# Connector_Sheet.net
KiCad netlist of a schematic drawn in Altium Designer
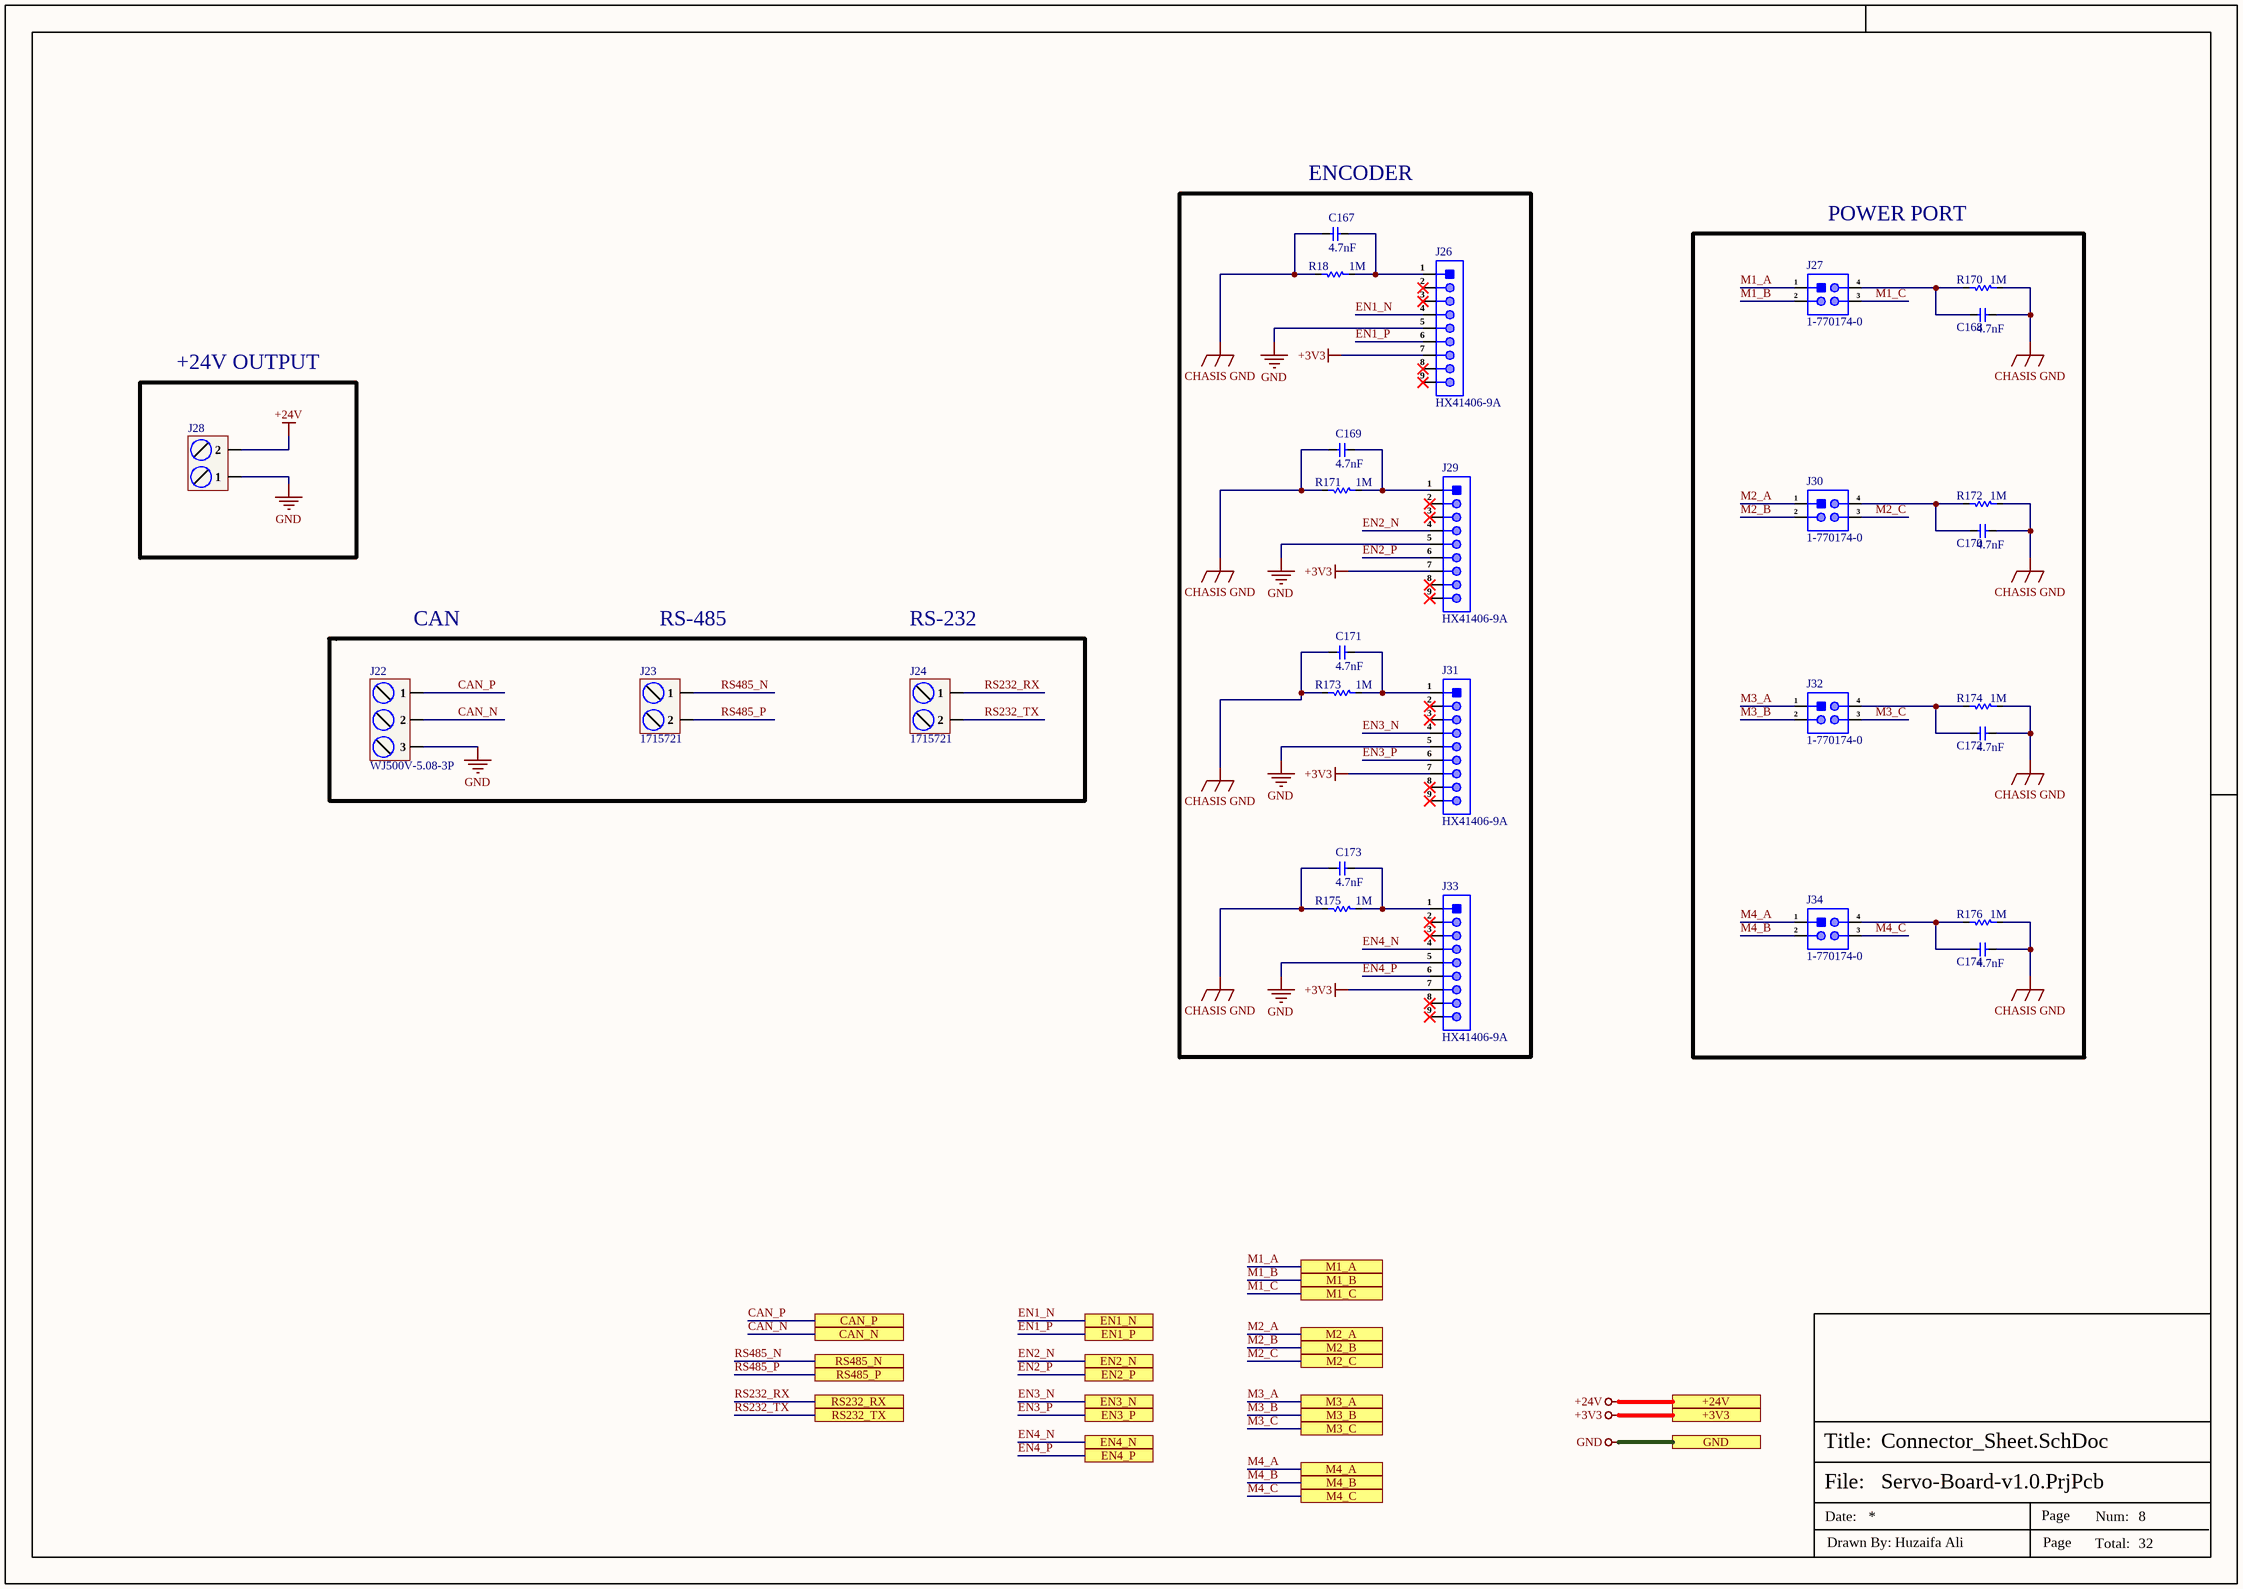
[diagram p0: Connector_Sheet.SchDoc]

(export (version "E")
  (design (tool "Eeschema 10.0.6"))
  (components
    (comp (ref "C167")
      (value "4.7nF")
      (footprint "Cap-0603")
      (description "CAP CER 4700PF 50V C0G/NPO 0603")
      (fields
        (field (name "MANUFACTURER") "Yageo")
        (field (name "MANUFACTURER PART NUMBER") "CC0603JRNPO9BN472")
      )
      (libsource (lib "eSpark_centralized_Library(2022)") (part "CC0603JRNPO9BN472"))
    )
    (comp (ref "C168")
      (value "4.7nF")
      (footprint "Cap-0603")
      (description "CAP CER 4700PF 50V C0G/NPO 0603")
      (fields
        (field (name "MANUFACTURER") "Yageo")
        (field (name "MANUFACTURER PART NUMBER") "CC0603JRNPO9BN472")
      )
      (libsource (lib "eSpark_centralized_Library(2022)") (part "CC0603JRNPO9BN472"))
    )
    (comp (ref "C169")
      (value "4.7nF")
      (footprint "Cap-0603")
      (description "CAP CER 4700PF 50V C0G/NPO 0603")
      (fields
        (field (name "MANUFACTURER") "Yageo")
        (field (name "MANUFACTURER PART NUMBER") "CC0603JRNPO9BN472")
      )
      (libsource (lib "eSpark_centralized_Library(2022)") (part "CC0603JRNPO9BN472"))
    )
    (comp (ref "C170")
      (value "4.7nF")
      (footprint "Cap-0603")
      (description "CAP CER 4700PF 50V C0G/NPO 0603")
      (fields
        (field (name "MANUFACTURER") "Yageo")
        (field (name "MANUFACTURER PART NUMBER") "CC0603JRNPO9BN472")
      )
      (libsource (lib "eSpark_centralized_Library(2022)") (part "CC0603JRNPO9BN472"))
    )
    (comp (ref "C171")
      (value "4.7nF")
      (footprint "Cap-0603")
      (description "CAP CER 4700PF 50V C0G/NPO 0603")
      (fields
        (field (name "MANUFACTURER") "Yageo")
        (field (name "MANUFACTURER PART NUMBER") "CC0603JRNPO9BN472")
      )
      (libsource (lib "eSpark_centralized_Library(2022)") (part "CC0603JRNPO9BN472"))
    )
    (comp (ref "C172")
      (value "4.7nF")
      (footprint "Cap-0603")
      (description "CAP CER 4700PF 50V C0G/NPO 0603")
      (fields
        (field (name "MANUFACTURER") "Yageo")
        (field (name "MANUFACTURER PART NUMBER") "CC0603JRNPO9BN472")
      )
      (libsource (lib "eSpark_centralized_Library(2022)") (part "CC0603JRNPO9BN472"))
    )
    (comp (ref "C173")
      (value "4.7nF")
      (footprint "Cap-0603")
      (description "CAP CER 4700PF 50V C0G/NPO 0603")
      (fields
        (field (name "MANUFACTURER") "Yageo")
        (field (name "MANUFACTURER PART NUMBER") "CC0603JRNPO9BN472")
      )
      (libsource (lib "eSpark_centralized_Library(2022)") (part "CC0603JRNPO9BN472"))
    )
    (comp (ref "C174")
      (value "4.7nF")
      (footprint "Cap-0603")
      (description "CAP CER 4700PF 50V C0G/NPO 0603")
      (fields
        (field (name "MANUFACTURER") "Yageo")
        (field (name "MANUFACTURER PART NUMBER") "CC0603JRNPO9BN472")
      )
      (libsource (lib "eSpark_centralized_Library(2022)") (part "CC0603JRNPO9BN472"))
    )
    (comp (ref "J22")
      (value "WJ500V-5.08-3P")
      (footprint "WJ500V-5.08-3P")
      (fields (field (name "MANUFACTURER") "Ningbo Kangnex Elec") (field (name "LCSC PART NUMBER") "C72334"))
      (libsource (lib "eSpark Libraries") (part "WJ500V-5.08-3P"))
    )
    (comp (ref "J23")
      (value "1715721")
      (footprint "1715721")
      (description "TERM BLK 2P SIDE ENT 5.08MM PCB")
      (fields (field (name "MANUFACTURER") "Phoenix Contact"))
      (libsource (lib "eSpark Libraries") (part "1715721"))
    )
    (comp (ref "J24")
      (value "1715721")
      (footprint "1715721")
      (description "TERM BLK 2P SIDE ENT 5.08MM PCB")
      (fields (field (name "MANUFACTURER") "Phoenix Contact"))
      (libsource (lib "eSpark Libraries") (part "1715721"))
    )
    (comp (ref "J26")
      (value "HX41406-9A")
      (footprint "HX41406-9A")
      (description "3x3P 9P 3 4.14mm 4.14mm 3 -25℃~+105℃ 8A Straight Plugin,P=4.14mm Wire To Board Connector ROHS")
      (fields
        (field (name "MANUFACTURER") "HX(Zhejiang Yueqing Hongxing Elec)")
        (field (name "LCSC PART NUMBER") "C704507")
      )
      (libsource (lib "eSpark Libraries") (part "HX41406-9A"))
    )
    (comp (ref "J27")
      (value "1-770174-0")
      (footprint "1-770174-0")
      (description "CONN HEADER VERT 4POS 4.14MM")
      (fields (field (name "MANUFACTURER") "TE Connectivity"))
      (libsource (lib "eSpark Libraries") (part "1-770174-0"))
    )
    (comp (ref "J28")
      (value "MXHB9500-9.5-02P-BK01-Cu-S-A")
      (footprint "MXHB9500-9.5-02P-BK01-Cu-S-A")
      (fields (field (name "MANUFACTURER") "MAX") (field (name "LCSC PART NUMBER") "C7542168"))
      (libsource (lib "eSpark Libraries") (part "MXHB9500-9.5-02P-BK01-Cu-S-A"))
    )
    (comp (ref "J29")
      (value "HX41406-9A")
      (footprint "HX41406-9A")
      (description "3x3P 9P 3 4.14mm 4.14mm 3 -25℃~+105℃ 8A Straight Plugin,P=4.14mm Wire To Board Connector ROHS")
      (fields
        (field (name "MANUFACTURER") "HX(Zhejiang Yueqing Hongxing Elec)")
        (field (name "LCSC PART NUMBER") "C704507")
      )
      (libsource (lib "eSpark Libraries") (part "HX41406-9A"))
    )
    (comp (ref "J30")
      (value "1-770174-0")
      (footprint "1-770174-0")
      (description "CONN HEADER VERT 4POS 4.14MM")
      (fields (field (name "MANUFACTURER") "TE Connectivity"))
      (libsource (lib "eSpark Libraries") (part "1-770174-0"))
    )
    (comp (ref "J31")
      (value "HX41406-9A")
      (footprint "HX41406-9A")
      (description "3x3P 9P 3 4.14mm 4.14mm 3 -25℃~+105℃ 8A Straight Plugin,P=4.14mm Wire To Board Connector ROHS")
      (fields
        (field (name "MANUFACTURER") "HX(Zhejiang Yueqing Hongxing Elec)")
        (field (name "LCSC PART NUMBER") "C704507")
      )
      (libsource (lib "eSpark Libraries") (part "HX41406-9A"))
    )
    (comp (ref "J32")
      (value "1-770174-0")
      (footprint "1-770174-0")
      (description "CONN HEADER VERT 4POS 4.14MM")
      (fields (field (name "MANUFACTURER") "TE Connectivity"))
      (libsource (lib "eSpark Libraries") (part "1-770174-0"))
    )
    (comp (ref "J33")
      (value "HX41406-9A")
      (footprint "HX41406-9A")
      (description "3x3P 9P 3 4.14mm 4.14mm 3 -25℃~+105℃ 8A Straight Plugin,P=4.14mm Wire To Board Connector ROHS")
      (fields
        (field (name "MANUFACTURER") "HX(Zhejiang Yueqing Hongxing Elec)")
        (field (name "LCSC PART NUMBER") "C704507")
      )
      (libsource (lib "eSpark Libraries") (part "HX41406-9A"))
    )
    (comp (ref "J34")
      (value "1-770174-0")
      (footprint "1-770174-0")
      (description "CONN HEADER VERT 4POS 4.14MM")
      (fields (field (name "MANUFACTURER") "TE Connectivity"))
      (libsource (lib "eSpark Libraries") (part "1-770174-0"))
    )
    (comp (ref "R18")
      (value "1M")
      (footprint "Res-0402")
      (description "RES SMD 1M OHM 5% 1/16W 0402")
      (fields
        (field (name "MANUFACTURER") "Yageo")
        (field (name "MANUFACTURER PART NUMBER") "AF0402JR-071ML")
      )
      (libsource (lib "eSpark_centralized_Library(2022)") (part "AF0402JR-071ML"))
    )
    (comp (ref "R170")
      (value "1M")
      (footprint "Res-0402")
      (description "RES SMD 1M OHM 5% 1/16W 0402")
      (fields
        (field (name "MANUFACTURER") "Yageo")
        (field (name "MANUFACTURER PART NUMBER") "AF0402JR-071ML")
      )
      (libsource (lib "eSpark_centralized_Library(2022)") (part "AF0402JR-071ML"))
    )
    (comp (ref "R171")
      (value "1M")
      (footprint "Res-0402")
      (description "RES SMD 1M OHM 5% 1/16W 0402")
      (fields
        (field (name "MANUFACTURER") "Yageo")
        (field (name "MANUFACTURER PART NUMBER") "AF0402JR-071ML")
      )
      (libsource (lib "eSpark_centralized_Library(2022)") (part "AF0402JR-071ML"))
    )
    (comp (ref "R172")
      (value "1M")
      (footprint "Res-0402")
      (description "RES SMD 1M OHM 5% 1/16W 0402")
      (fields
        (field (name "MANUFACTURER") "Yageo")
        (field (name "MANUFACTURER PART NUMBER") "AF0402JR-071ML")
      )
      (libsource (lib "eSpark_centralized_Library(2022)") (part "AF0402JR-071ML"))
    )
    (comp (ref "R173")
      (value "1M")
      (footprint "Res-0402")
      (description "RES SMD 1M OHM 5% 1/16W 0402")
      (fields
        (field (name "MANUFACTURER") "Yageo")
        (field (name "MANUFACTURER PART NUMBER") "AF0402JR-071ML")
      )
      (libsource (lib "eSpark_centralized_Library(2022)") (part "AF0402JR-071ML"))
    )
    (comp (ref "R174")
      (value "1M")
      (footprint "Res-0402")
      (description "RES SMD 1M OHM 5% 1/16W 0402")
      (fields
        (field (name "MANUFACTURER") "Yageo")
        (field (name "MANUFACTURER PART NUMBER") "AF0402JR-071ML")
      )
      (libsource (lib "eSpark_centralized_Library(2022)") (part "AF0402JR-071ML"))
    )
    (comp (ref "R175")
      (value "1M")
      (footprint "Res-0402")
      (description "RES SMD 1M OHM 5% 1/16W 0402")
      (fields
        (field (name "MANUFACTURER") "Yageo")
        (field (name "MANUFACTURER PART NUMBER") "AF0402JR-071ML")
      )
      (libsource (lib "eSpark_centralized_Library(2022)") (part "AF0402JR-071ML"))
    )
    (comp (ref "R176")
      (value "1M")
      (footprint "Res-0402")
      (description "RES SMD 1M OHM 5% 1/16W 0402")
      (fields
        (field (name "MANUFACTURER") "Yageo")
        (field (name "MANUFACTURER PART NUMBER") "AF0402JR-071ML")
      )
      (libsource (lib "eSpark_centralized_Library(2022)") (part "AF0402JR-071ML"))
    )
  )
  (nets
    (net (code "1") (name "+3V3") (class "Default")
      (node (ref "J26") (pin "7") (pinfunction "7_7") (pintype "passive"))
      (node (ref "J29") (pin "7") (pinfunction "7_7") (pintype "passive"))
      (node (ref "J31") (pin "7") (pinfunction "7_7") (pintype "passive"))
      (node (ref "J33") (pin "7") (pinfunction "7_7") (pintype "passive"))
    )
    (net (code "2") (name "+24V") (class "Default")
      (node (ref "J28") (pin "2") (pinfunction "2_2") (pintype "passive"))
    )
    (net (code "3") (name "/CAN_N") (class "Default")
      (node (ref "J22") (pin "2") (pinfunction "2_2") (pintype "passive"))
    )
    (net (code "4") (name "/CAN_P") (class "Default")
      (node (ref "J22") (pin "1") (pinfunction "1_1") (pintype "passive"))
    )
    (net (code "5") (name "/EN1_N") (class "Default")
      (node (ref "J26") (pin "4") (pinfunction "4_4") (pintype "passive"))
    )
    (net (code "6") (name "/EN1_P") (class "Default")
      (node (ref "J26") (pin "6") (pinfunction "6_6") (pintype "passive"))
    )
    (net (code "7") (name "/EN2_N") (class "Default")
      (node (ref "J29") (pin "4") (pinfunction "4_4") (pintype "passive"))
    )
    (net (code "8") (name "/EN2_P") (class "Default")
      (node (ref "J29") (pin "6") (pinfunction "6_6") (pintype "passive"))
    )
    (net (code "9") (name "/EN3_N") (class "Default")
      (node (ref "J31") (pin "4") (pinfunction "4_4") (pintype "passive"))
    )
    (net (code "10") (name "/EN3_P") (class "Default")
      (node (ref "J31") (pin "6") (pinfunction "6_6") (pintype "passive"))
    )
    (net (code "11") (name "/EN4_N") (class "Default")
      (node (ref "J33") (pin "4") (pinfunction "4_4") (pintype "passive"))
    )
    (net (code "12") (name "/EN4_P") (class "Default")
      (node (ref "J33") (pin "6") (pinfunction "6_6") (pintype "passive"))
    )
    (net (code "13") (name "/M1_A") (class "Default")
      (node (ref "J27") (pin "1") (pinfunction "1_1") (pintype "passive"))
    )
    (net (code "14") (name "/M1_B") (class "Default")
      (node (ref "J27") (pin "2") (pinfunction "2_2") (pintype "passive"))
    )
    (net (code "15") (name "/M1_C") (class "Default")
      (node (ref "J27") (pin "3") (pinfunction "3_3") (pintype "passive"))
    )
    (net (code "16") (name "/M2_A") (class "Default")
      (node (ref "J30") (pin "1") (pinfunction "1_1") (pintype "passive"))
    )
    (net (code "17") (name "/M2_B") (class "Default")
      (node (ref "J30") (pin "2") (pinfunction "2_2") (pintype "passive"))
    )
    (net (code "18") (name "/M2_C") (class "Default")
      (node (ref "J30") (pin "3") (pinfunction "3_3") (pintype "passive"))
    )
    (net (code "19") (name "/M3_A") (class "Default")
      (node (ref "J32") (pin "1") (pinfunction "1_1") (pintype "passive"))
    )
    (net (code "20") (name "/M3_B") (class "Default")
      (node (ref "J32") (pin "2") (pinfunction "2_2") (pintype "passive"))
    )
    (net (code "21") (name "/M3_C") (class "Default")
      (node (ref "J32") (pin "3") (pinfunction "3_3") (pintype "passive"))
    )
    (net (code "22") (name "/M4_A") (class "Default")
      (node (ref "J34") (pin "1") (pinfunction "1_1") (pintype "passive"))
    )
    (net (code "23") (name "/M4_B") (class "Default")
      (node (ref "J34") (pin "2") (pinfunction "2_2") (pintype "passive"))
    )
    (net (code "24") (name "/M4_C") (class "Default")
      (node (ref "J34") (pin "3") (pinfunction "3_3") (pintype "passive"))
    )
    (net (code "25") (name "/RS232_RX") (class "Default")
      (node (ref "J24") (pin "1") (pinfunction "1_1") (pintype "passive"))
    )
    (net (code "26") (name "/RS232_TX") (class "Default")
      (node (ref "J24") (pin "2") (pinfunction "2_2") (pintype "passive"))
    )
    (net (code "27") (name "/RS485_N") (class "Default")
      (node (ref "J23") (pin "1") (pinfunction "1_1") (pintype "passive"))
    )
    (net (code "28") (name "/RS485_P") (class "Default")
      (node (ref "J23") (pin "2") (pinfunction "2_2") (pintype "passive"))
    )
    (net (code "29") (name "CHASIS GND") (class "Default")
      (node (ref "C167") (pin "2") (pinfunction "2_2") (pintype "passive"))
      (node (ref "C168") (pin "2") (pinfunction "2_2") (pintype "passive"))
      (node (ref "C169") (pin "2") (pinfunction "2_2") (pintype "passive"))
      (node (ref "C170") (pin "2") (pinfunction "2_2") (pintype "passive"))
      (node (ref "C171") (pin "2") (pinfunction "2_2") (pintype "passive"))
      (node (ref "C172") (pin "2") (pinfunction "2_2") (pintype "passive"))
      (node (ref "C173") (pin "2") (pinfunction "2_2") (pintype "passive"))
      (node (ref "C174") (pin "2") (pinfunction "2_2") (pintype "passive"))
      (node (ref "R170") (pin "2") (pinfunction "2_2") (pintype "passive"))
      (node (ref "R171") (pin "1") (pinfunction "1_1") (pintype "passive"))
      (node (ref "R172") (pin "2") (pinfunction "2_2") (pintype "passive"))
      (node (ref "R173") (pin "1") (pinfunction "1_1") (pintype "passive"))
      (node (ref "R174") (pin "2") (pinfunction "2_2") (pintype "passive"))
      (node (ref "R175") (pin "1") (pinfunction "1_1") (pintype "passive"))
      (node (ref "R176") (pin "2") (pinfunction "2_2") (pintype "passive"))
      (node (ref "R18") (pin "1") (pinfunction "1_1") (pintype "passive"))
    )
    (net (code "30") (name "GND") (class "Default")
      (node (ref "J22") (pin "3") (pinfunction "3_3") (pintype "passive"))
      (node (ref "J26") (pin "5") (pinfunction "5_5") (pintype "passive"))
      (node (ref "J28") (pin "1") (pinfunction "1_1") (pintype "passive"))
      (node (ref "J29") (pin "5") (pinfunction "5_5") (pintype "passive"))
      (node (ref "J31") (pin "5") (pinfunction "5_5") (pintype "passive"))
      (node (ref "J33") (pin "5") (pinfunction "5_5") (pintype "passive"))
    )
    (net (code "31") (name "Net-(C167-Pad1)") (class "Default")
      (node (ref "C167") (pin "1") (pinfunction "1_1") (pintype "passive"))
      (node (ref "J26") (pin "1") (pinfunction "1_1") (pintype "passive"))
      (node (ref "R18") (pin "2") (pinfunction "2_2") (pintype "passive"))
    )
    (net (code "32") (name "Net-(C168-Pad1)") (class "Default")
      (node (ref "C168") (pin "1") (pinfunction "1_1") (pintype "passive"))
      (node (ref "J27") (pin "4") (pinfunction "4_4") (pintype "passive"))
      (node (ref "R170") (pin "1") (pinfunction "1_1") (pintype "passive"))
    )
    (net (code "33") (name "Net-(C169-Pad1)") (class "Default")
      (node (ref "C169") (pin "1") (pinfunction "1_1") (pintype "passive"))
      (node (ref "J29") (pin "1") (pinfunction "1_1") (pintype "passive"))
      (node (ref "R171") (pin "2") (pinfunction "2_2") (pintype "passive"))
    )
    (net (code "34") (name "Net-(C170-Pad1)") (class "Default")
      (node (ref "C170") (pin "1") (pinfunction "1_1") (pintype "passive"))
      (node (ref "J30") (pin "4") (pinfunction "4_4") (pintype "passive"))
      (node (ref "R172") (pin "1") (pinfunction "1_1") (pintype "passive"))
    )
    (net (code "35") (name "Net-(C171-Pad1)") (class "Default")
      (node (ref "C171") (pin "1") (pinfunction "1_1") (pintype "passive"))
      (node (ref "J31") (pin "1") (pinfunction "1_1") (pintype "passive"))
      (node (ref "R173") (pin "2") (pinfunction "2_2") (pintype "passive"))
    )
    (net (code "36") (name "Net-(C172-Pad1)") (class "Default")
      (node (ref "C172") (pin "1") (pinfunction "1_1") (pintype "passive"))
      (node (ref "J32") (pin "4") (pinfunction "4_4") (pintype "passive"))
      (node (ref "R174") (pin "1") (pinfunction "1_1") (pintype "passive"))
    )
    (net (code "37") (name "Net-(C173-Pad1)") (class "Default")
      (node (ref "C173") (pin "1") (pinfunction "1_1") (pintype "passive"))
      (node (ref "J33") (pin "1") (pinfunction "1_1") (pintype "passive"))
      (node (ref "R175") (pin "2") (pinfunction "2_2") (pintype "passive"))
    )
    (net (code "38") (name "Net-(C174-Pad1)") (class "Default")
      (node (ref "C174") (pin "1") (pinfunction "1_1") (pintype "passive"))
      (node (ref "J34") (pin "4") (pinfunction "4_4") (pintype "passive"))
      (node (ref "R176") (pin "1") (pinfunction "1_1") (pintype "passive"))
    )
    (net (code "39") (name "unconnected-(J26-Pad2)") (class "Default")
      (node (ref "J26") (pin "2") (pinfunction "2_2") (pintype "passive+no_connect"))
    )
    (net (code "40") (name "unconnected-(J26-Pad3)") (class "Default")
      (node (ref "J26") (pin "3") (pinfunction "3_3") (pintype "passive+no_connect"))
    )
    (net (code "41") (name "unconnected-(J26-Pad8)") (class "Default")
      (node (ref "J26") (pin "8") (pinfunction "8_8") (pintype "passive+no_connect"))
    )
    (net (code "42") (name "unconnected-(J26-Pad9)") (class "Default")
      (node (ref "J26") (pin "9") (pinfunction "9_9") (pintype "passive+no_connect"))
    )
    (net (code "43") (name "unconnected-(J29-Pad2)") (class "Default")
      (node (ref "J29") (pin "2") (pinfunction "2_2") (pintype "passive+no_connect"))
    )
    (net (code "44") (name "unconnected-(J29-Pad3)") (class "Default")
      (node (ref "J29") (pin "3") (pinfunction "3_3") (pintype "passive+no_connect"))
    )
    (net (code "45") (name "unconnected-(J29-Pad8)") (class "Default")
      (node (ref "J29") (pin "8") (pinfunction "8_8") (pintype "passive+no_connect"))
    )
    (net (code "46") (name "unconnected-(J29-Pad9)") (class "Default")
      (node (ref "J29") (pin "9") (pinfunction "9_9") (pintype "passive+no_connect"))
    )
    (net (code "47") (name "unconnected-(J31-Pad2)") (class "Default")
      (node (ref "J31") (pin "2") (pinfunction "2_2") (pintype "passive+no_connect"))
    )
    (net (code "48") (name "unconnected-(J31-Pad3)") (class "Default")
      (node (ref "J31") (pin "3") (pinfunction "3_3") (pintype "passive+no_connect"))
    )
    (net (code "49") (name "unconnected-(J31-Pad8)") (class "Default")
      (node (ref "J31") (pin "8") (pinfunction "8_8") (pintype "passive+no_connect"))
    )
    (net (code "50") (name "unconnected-(J31-Pad9)") (class "Default")
      (node (ref "J31") (pin "9") (pinfunction "9_9") (pintype "passive+no_connect"))
    )
    (net (code "51") (name "unconnected-(J33-Pad2)") (class "Default")
      (node (ref "J33") (pin "2") (pinfunction "2_2") (pintype "passive+no_connect"))
    )
    (net (code "52") (name "unconnected-(J33-Pad3)") (class "Default")
      (node (ref "J33") (pin "3") (pinfunction "3_3") (pintype "passive+no_connect"))
    )
    (net (code "53") (name "unconnected-(J33-Pad8)") (class "Default")
      (node (ref "J33") (pin "8") (pinfunction "8_8") (pintype "passive+no_connect"))
    )
    (net (code "54") (name "unconnected-(J33-Pad9)") (class "Default")
      (node (ref "J33") (pin "9") (pinfunction "9_9") (pintype "passive+no_connect"))
    )
  )
)
